# STM32_Schematics.net
KiCad netlist of a schematic drawn in Altium Designer
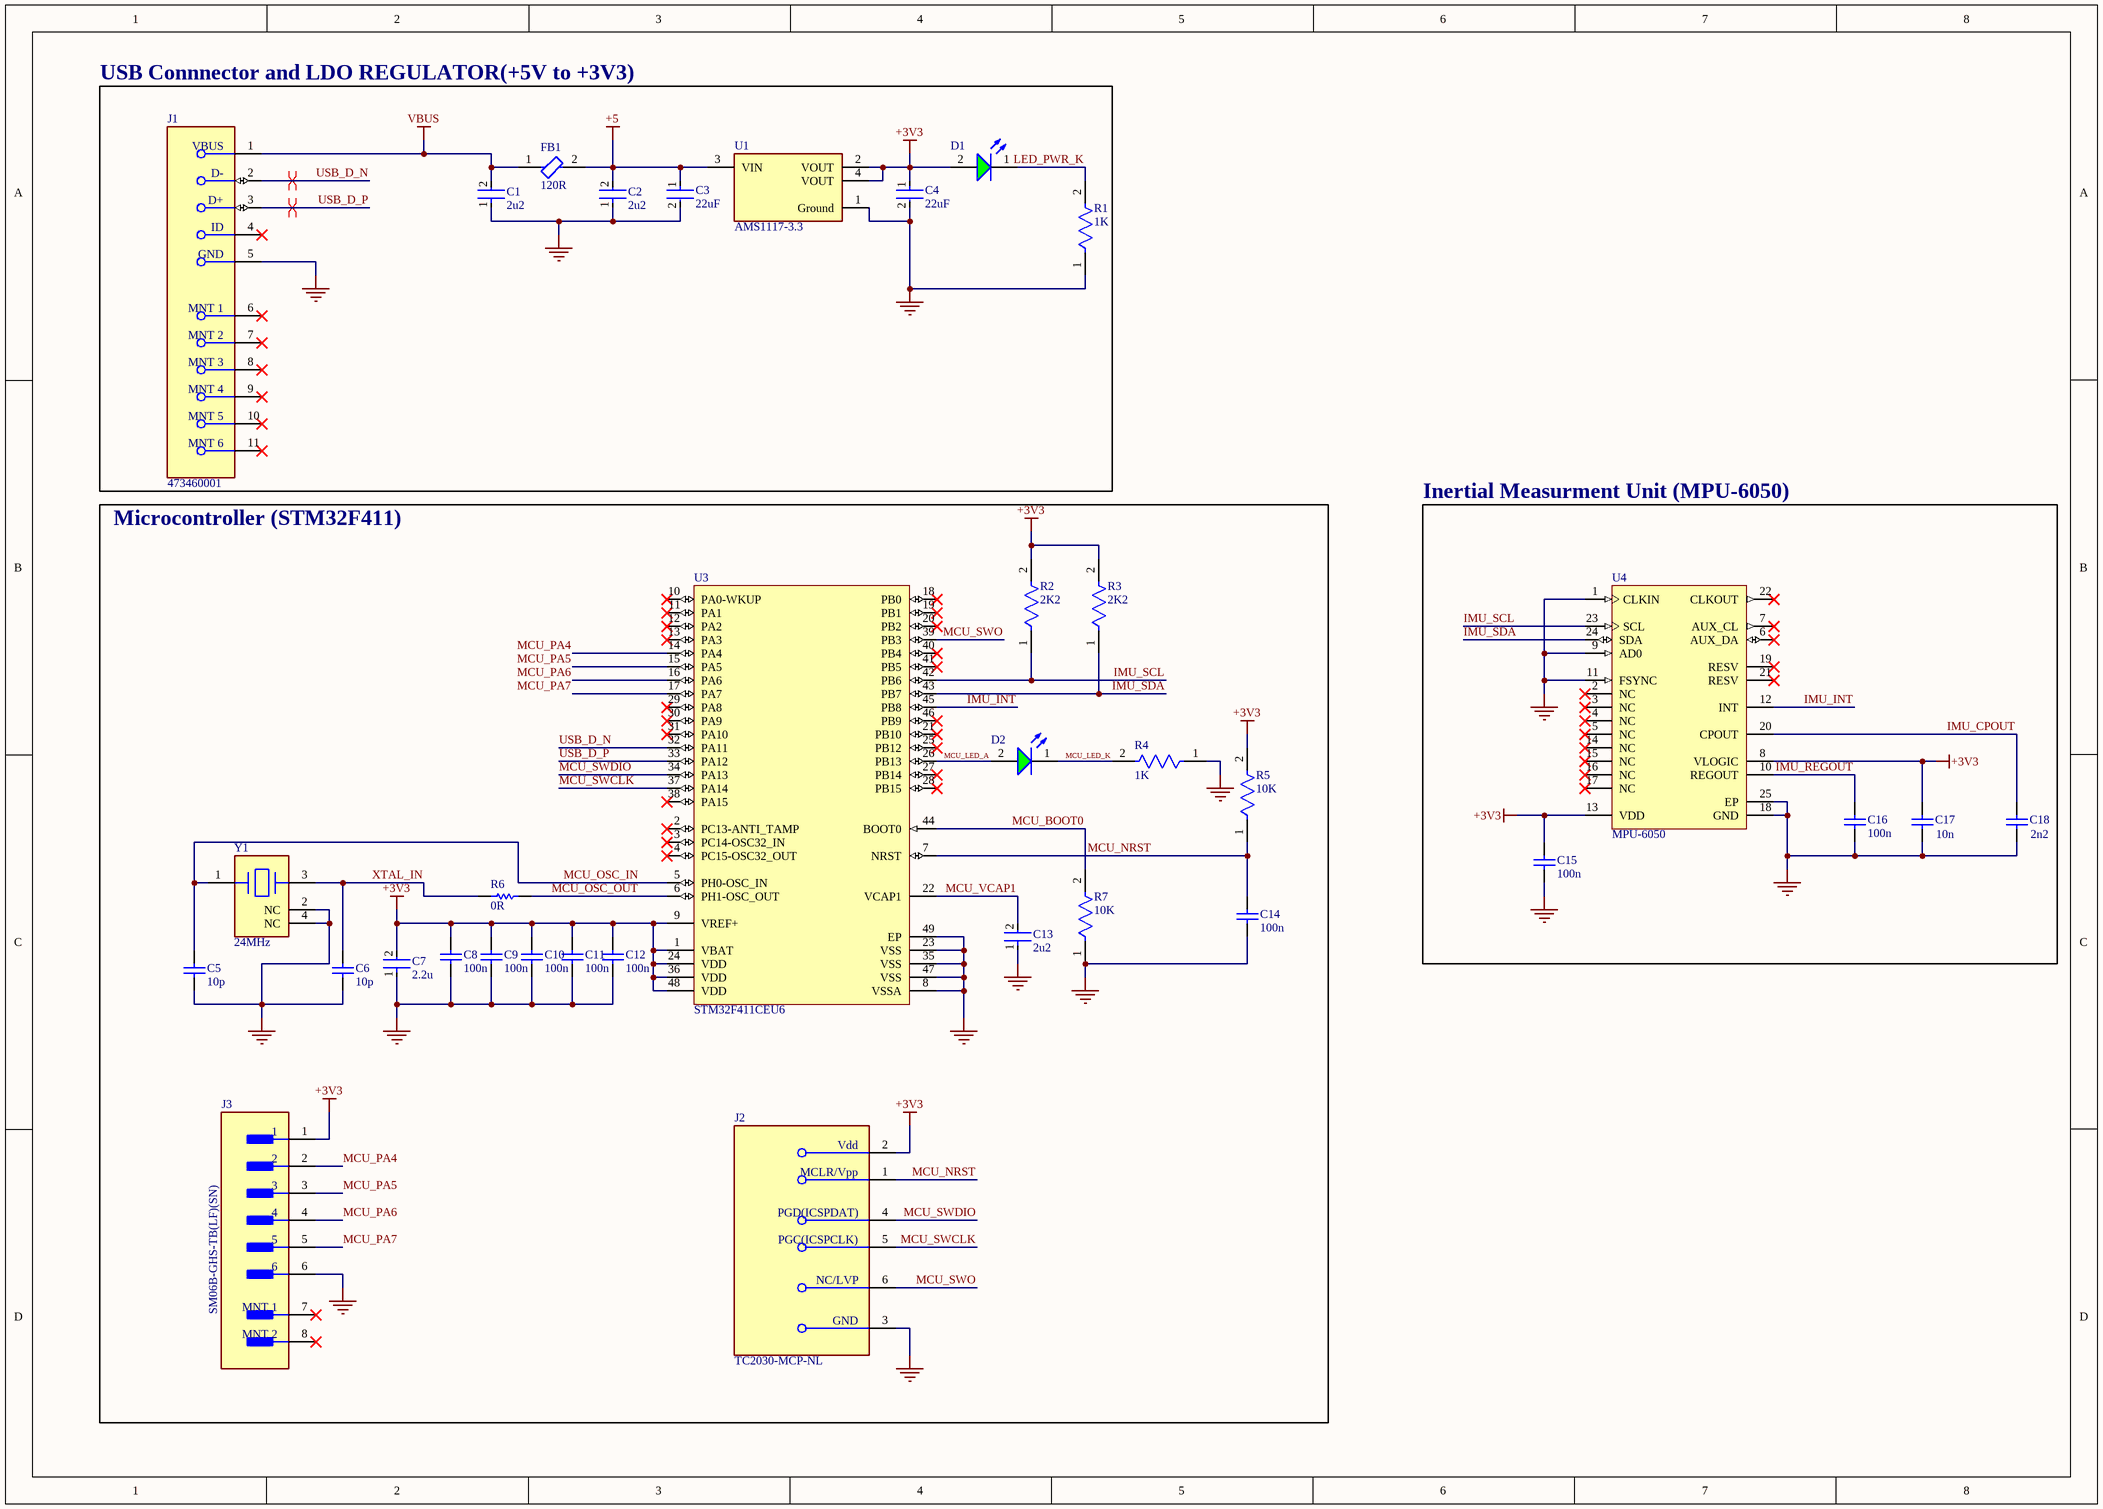
[diagram p0: STM32_Schematics.SchDoc]

(export (version "E")
  (design (tool "Eeschema 10.0.6"))
  (components
    (comp (ref "C1")
      (value "2u2")
      (footprint "FP-GRM188-0_2-IPC_B")
      (description "CAP CER 2.2UF 16V X7S 0603")
      (fields (field (name "TOLERANCE") "10%"))
      (libsource (lib "Altium Content Vault") (part "b4654b650e69147ec39a6b967a45e02"))
    )
    (comp (ref "C2")
      (value "2u2")
      (footprint "FP-GRM188-0_2-IPC_B")
      (description "CAP CER 2.2UF 16V X7S 0603")
      (fields (field (name "TOLERANCE") "10%"))
      (libsource (lib "Altium Content Vault") (part "b4654b650e69147ec39a6b967a45e02"))
    )
    (comp (ref "C3")
      (value "22uF")
      (footprint "FP-GRM219-0_2-0_15-IPC_B")
      (description "Chip Multilayer Ceramic Capacitors for General Purpose, 0805, 22uF, X5R, 15%, 20%, 16V")
      (fields (field (name "TOLERANCE") "20%"))
      (libsource (lib "Altium Content Vault") (part "b4654b650e69147ec39a6b967a45e02"))
    )
    (comp (ref "C4")
      (value "22uF")
      (footprint "FP-GRM219-0_2-0_15-IPC_B")
      (description "Chip Multilayer Ceramic Capacitors for General Purpose, 0805, 22uF, X5R, 15%, 20%, 16V")
      (fields (field (name "TOLERANCE") "20%"))
      (libsource (lib "Altium Content Vault") (part "b4654b650e69147ec39a6b967a45e02"))
    )
    (comp (ref "C5")
      (value "10p")
      (footprint "CAPC1005X55X25NL05T05")
      (fields (field (name "PART NUMBER") "VJ0402A100FXQCW1BC") (field (name "MANUFACTURER") "Vitramon"))
      (libsource (lib "Altium Content Vault") (part "CAP"))
    )
    (comp (ref "C6")
      (value "10p")
      (footprint "CAPC1005X55X25NL05T05")
      (fields (field (name "PART NUMBER") "VJ0402A100FXQCW1BC") (field (name "MANUFACTURER") "Vitramon"))
      (libsource (lib "Altium Content Vault") (part "CAP"))
    )
    (comp (ref "C7")
      (value "2.2u")
      (footprint "FP-GRM188-0_2-IPC_B")
      (description "CAP CER 2.2UF 16V X7S 0603")
      (fields (field (name "TOLERANCE") "10%"))
      (libsource (lib "Altium Content Vault") (part "b4654b650e69147ec39a6b967a45e02"))
    )
    (comp (ref "C8")
      (value "100n")
      (footprint "CAPC1050X55X23ML05T13")
      (description "Chip Capacitor, 100 nF, +/- 10%, 16 V, -55 to 125 degC, 0402 (1005 Metric), RoHS, Tape and Reel")
      (fields (field (name "MANUFACTURER") "Samsung Electro-Mechanics"))
      (libsource (lib "Altium Content Vault") (part "CAP-NP-2"))
    )
    (comp (ref "C9")
      (value "100n")
      (footprint "CAPC1050X55X23ML05T13")
      (description "Chip Capacitor, 100 nF, +/- 10%, 16 V, -55 to 125 degC, 0402 (1005 Metric), RoHS, Tape and Reel")
      (fields (field (name "MANUFACTURER") "Samsung Electro-Mechanics"))
      (libsource (lib "Altium Content Vault") (part "CAP-NP-2"))
    )
    (comp (ref "C10")
      (value "100n")
      (footprint "CAPC1050X55X23ML05T13")
      (description "Chip Capacitor, 100 nF, +/- 10%, 16 V, -55 to 125 degC, 0402 (1005 Metric), RoHS, Tape and Reel")
      (fields (field (name "MANUFACTURER") "Samsung Electro-Mechanics"))
      (libsource (lib "Altium Content Vault") (part "CAP-NP-2"))
    )
    (comp (ref "C11")
      (value "100n")
      (footprint "CAPC1050X55X23ML05T13")
      (description "Chip Capacitor, 100 nF, +/- 10%, 16 V, -55 to 125 degC, 0402 (1005 Metric), RoHS, Tape and Reel")
      (fields (field (name "MANUFACTURER") "Samsung Electro-Mechanics"))
      (libsource (lib "Altium Content Vault") (part "CAP-NP-2"))
    )
    (comp (ref "C12")
      (value "100n")
      (footprint "CAPC1050X55X23ML05T13")
      (description "Chip Capacitor, 100 nF, +/- 10%, 16 V, -55 to 125 degC, 0402 (1005 Metric), RoHS, Tape and Reel")
      (fields (field (name "MANUFACTURER") "Samsung Electro-Mechanics"))
      (libsource (lib "Altium Content Vault") (part "CAP-NP-2"))
    )
    (comp (ref "C13")
      (value "2u2")
      (footprint "FP-GRM188-0_2-IPC_B")
      (description "CAP CER 2.2UF 16V X7S 0603")
      (fields (field (name "TOLERANCE") "10%"))
      (libsource (lib "Altium Content Vault") (part "b4654b650e69147ec39a6b967a45e02"))
    )
    (comp (ref "C14")
      (value "100n")
      (footprint "CAPC1050X55X23ML05T13")
      (description "Chip Capacitor, 100 nF, +/- 10%, 16 V, -55 to 125 degC, 0402 (1005 Metric), RoHS, Tape and Reel")
      (fields (field (name "MANUFACTURER") "Samsung Electro-Mechanics"))
      (libsource (lib "Altium Content Vault") (part "CAP-NP-2"))
    )
    (comp (ref "C15")
      (value "100n")
      (footprint "CAPC1050X55X23ML05T13")
      (description "Chip Capacitor, 100 nF, +/- 10%, 16 V, -55 to 125 degC, 0402 (1005 Metric), RoHS, Tape and Reel")
      (fields (field (name "MANUFACTURER") "Samsung Electro-Mechanics"))
      (libsource (lib "Altium Content Vault") (part "CAP-NP-2"))
    )
    (comp (ref "C16")
      (value "100n")
      (footprint "CAPC1050X55X23ML05T13")
      (description "Chip Capacitor, 100 nF, +/- 10%, 16 V, -55 to 125 degC, 0402 (1005 Metric), RoHS, Tape and Reel")
      (fields (field (name "MANUFACTURER") "Samsung Electro-Mechanics"))
      (libsource (lib "Altium Content Vault") (part "CAP-NP-2"))
    )
    (comp (ref "C17")
      (value "10n")
      (footprint "CAPC1005X55X25LL05T10")
      (description "Chip Capacitor, 10 nF, 16 V, 10%, -55 to 125 degC, 0402 (1005 Metric), RoHS, Tape and Reel")
      (fields (field (name "MANUFACTURER") "Murata"))
      (libsource (lib "Altium Content Vault") (part "CAP-NP-2"))
    )
    (comp (ref "C18")
      (value "2n2")
      (footprint "CAPC1005X55X25LL05T10")
      (description "Chip Capacitor, 2.2nF, 16 V, 10%, -55 to 125 degC, 0402 (1005 Metric), RoHS, Tape and Reel")
      (fields (field (name "MANUFACTURER") "Murata"))
      (libsource (lib "Altium Content Vault") (part "CAP-NP-2"))
    )
    (comp (ref "D1")
      (value "150040VS73240")
      (footprint "WL-SMCC_0402_L1W0.5H0.4")
      (description "Wurth Elektronik LED, WL-SMCC, 1005 (0402), 570 nm, 1 x 0.5 x 0.4mm")
      (libsource (lib "Altium Content Vault") (part "LED_Green_2A-1K"))
    )
    (comp (ref "D2")
      (value "150040VS73240")
      (footprint "WL-SMCC_0402_L1W0.5H0.4")
      (description "Wurth Elektronik LED, WL-SMCC, 1005 (0402), 570 nm, 1 x 0.5 x 0.4mm")
      (libsource (lib "Altium Content Vault") (part "LED_Green_2A-1K"))
    )
    (comp (ref "FB1")
      (value "120R")
      (footprint "FP-BLM18-0_15-t0_8-IPC_B")
      (description "Chip Ferrite Bead, 0603, 120Ω @ 100MHz, 0.18Ω, 25%, 800mA")
      (fields (field (name "TOLERANCE") "25%"))
      (libsource (lib "Altium Content Vault") (part "5f30dd21d616792df468990f7003faa"))
    )
    (comp (ref "J1")
      (value "473460001")
      (footprint "FP-473460001-MFG")
      (description "CONN RCPT USB2.0 MICRO B SMD R/A")
      (fields
        (field (name "OCTOPART") "https://octopart.com/47346-0001-molex-7164928")
        (field (name "MANUFACTURER") "Molex")
      )
      (libsource (lib "Altium Content Vault") (part "53ae1f1d9b557310b43ca686e5bb76a"))
    )
    (comp (ref "J2")
      (value "TC2030-MCP-NL")
      (footprint "FP-TC2030-MCP-NL-MFG")
      (description "CABLE TAG-CONNECT IN-CIRCUIT")
      (libsource (lib "Altium Content Vault") (part "da277a6d6cd793b3b4415b302df1337"))
    )
    (comp (ref "J3")
      (value "SM06B-GHS-TB(LF)(SN)")
      (footprint "FP-SM06B-GHS-TB_LF_SN-MFG")
      (description "CONN HEADER SMD R/A 6POS 1.25MM")
      (libsource (lib "Altium Content Vault") (part "ed24c53d9ba001d1a2a686240a95171"))
    )
    (comp (ref "R1")
      (value "1K")
      (footprint "FP-RC0402-0_4-IPC_A")
      (description "RES 1K OHM 1% 1/16W 0402")
      (fields (field (name "TOLERANCE") "1%"))
      (libsource (lib "Altium Content Vault") (part "1029c3af85768c4190bb7ad29bc67b5"))
    )
    (comp (ref "R2")
      (value "2K2")
      (footprint "FP-AC0402-IPC_C")
      (description "RES 2.2kΩ ±1% 0.125W 0402")
      (libsource (lib "Altium Content Vault") (part "1029c3af85768c4190bb7ad29bc67b5"))
    )
    (comp (ref "R3")
      (value "2K2")
      (footprint "FP-AC0402-IPC_C")
      (description "RES 2.2kΩ ±1% 0.125W 0402")
      (libsource (lib "Altium Content Vault") (part "1029c3af85768c4190bb7ad29bc67b5"))
    )
    (comp (ref "R4")
      (value "1K")
      (footprint "FP-RC0402-0_4-IPC_A")
      (description "RES 1K OHM 1% 1/16W 0402")
      (fields (field (name "TOLERANCE") "1%"))
      (libsource (lib "Altium Content Vault") (part "1029c3af85768c4190bb7ad29bc67b5"))
    )
    (comp (ref "R5")
      (value "10K")
      (footprint "FP-CRCW0402-C-e3-IPC_C")
      (description "RES 10K OHM 1% 1/16W 0402")
      (fields (field (name "TOLERANCE") "1%"))
      (libsource (lib "Altium Content Vault") (part "1029c3af85768c4190bb7ad29bc67b5"))
    )
    (comp (ref "R6")
      (value "0R")
      (footprint "RESC1005X40X25LL05T10")
      (description "Chip Resistor, 0 Ohm, +/- 5%, -55 to 125 degC, 0402 (1005 Metric), RoHS, Tape and Reel")
      (fields (field (name "MANUFACTURER") "Samsung Electro-Mechanics"))
      (libsource (lib "Altium Content Vault") (part "RES-2"))
    )
    (comp (ref "R7")
      (value "10K")
      (footprint "FP-CRCW0402-C-e3-IPC_C")
      (description "RES 10K OHM 1% 1/16W 0402")
      (fields (field (name "TOLERANCE") "1%"))
      (libsource (lib "Altium Content Vault") (part "1029c3af85768c4190bb7ad29bc67b5"))
    )
    (comp (ref "U1")
      (value "AMS1117-3.3")
      (footprint "FP-AMS1117-IPC_C")
      (description "LDO Voltage Regulators 1A, 3.3V")
      (fields
        (field (name "OCTOPART") "https://octopart.com/ams1117-3.3-advanced+monolithic+systems-25899300")
        (field (name "MANUFACTURER") "Advanced Monolithic Systems")
      )
      (libsource (lib "Altium Content Vault") (part "8bdbb5f8e77002000e30dd2845d0354"))
    )
    (comp (ref "U3")
      (value "STM32F411CEU6")
      (footprint "STM-UFQFPN48_L")
      (libsource (lib "Altium Content Vault") (part "MC-ARM-STM32F411-UFQFPN48"))
    )
    (comp (ref "U4")
      (value "MPU-6050")
      (footprint "IS-QFN-24_V")
      (fields (field (name "MANUFACTURER") "InvenSense"))
      (libsource (lib "Altium Content Vault") (part "IS-MPU-6050-QFN-24"))
    )
    (comp (ref "Y1")
      (value "24MHz")
      (footprint "FP-XRCGB_F_N-MFG")
      (description "CRYSTAL 24.0000MHZ 6PF SMD")
      (fields (field (name "TOLERANCE") "30ppm"))
      (libsource (lib "Altium Content Vault") (part "13d16a3a70fb0809ccfd81e284aeb9d"))
    )
  )
  (nets
    (net (code "1") (name "+3V3") (class "Default")
      (node (ref "C10") (pin "2") (pinfunction "2_2") (pintype "passive"))
      (node (ref "C11") (pin "2") (pinfunction "2_2") (pintype "passive"))
      (node (ref "C12") (pin "2") (pinfunction "2_2") (pintype "passive"))
      (node (ref "C15") (pin "2") (pinfunction "2_2") (pintype "passive"))
      (node (ref "C17") (pin "2") (pinfunction "2_2") (pintype "passive"))
      (node (ref "C4") (pin "1") (pinfunction "1_1") (pintype "passive"))
      (node (ref "C7") (pin "2") (pinfunction "2_2") (pintype "passive"))
      (node (ref "C8") (pin "2") (pinfunction "2_2") (pintype "passive"))
      (node (ref "C9") (pin "2") (pinfunction "2_2") (pintype "passive"))
      (node (ref "D1") (pin "2") (pinfunction "A_2") (pintype "passive"))
      (node (ref "J2") (pin "2") (pinfunction "Vdd_2") (pintype "passive"))
      (node (ref "J3") (pin "1") (pinfunction "1_1") (pintype "passive"))
      (node (ref "R2") (pin "2") (pinfunction "2_2") (pintype "passive"))
      (node (ref "R3") (pin "2") (pinfunction "2_2") (pintype "passive"))
      (node (ref "R5") (pin "2") (pinfunction "2_2") (pintype "passive"))
      (node (ref "U1") (pin "2") (pinfunction "VOUT_2") (pintype "passive"))
      (node (ref "U1") (pin "4") (pinfunction "VOUT_4") (pintype "passive"))
      (node (ref "U3") (pin "1") (pinfunction "VBAT_1") (pintype "power_in"))
      (node (ref "U3") (pin "24") (pinfunction "VDD_24") (pintype "power_in"))
      (node (ref "U3") (pin "36") (pinfunction "VDD_36") (pintype "power_in"))
      (node (ref "U3") (pin "48") (pinfunction "VDD_48") (pintype "power_in"))
      (node (ref "U3") (pin "9") (pinfunction "VREF+_9") (pintype "power_in"))
      (node (ref "U4") (pin "13") (pinfunction "VDD_13") (pintype "power_in"))
      (node (ref "U4") (pin "8") (pinfunction "VLOGIC_8") (pintype "power_in"))
    )
    (net (code "2") (name "+5") (class "Default")
      (node (ref "C2") (pin "2") (pinfunction "2_2") (pintype "passive"))
      (node (ref "C3") (pin "1") (pinfunction "1_1") (pintype "passive"))
      (node (ref "FB1") (pin "2") (pinfunction "2_2") (pintype "passive"))
      (node (ref "U1") (pin "3") (pinfunction "VIN_3") (pintype "power_in"))
    )
    (net (code "3") (name "/IMU_CPOUT") (class "Default")
      (node (ref "C18") (pin "2") (pinfunction "2_2") (pintype "passive"))
      (node (ref "U4") (pin "20") (pinfunction "CPOUT_20") (pintype "passive"))
    )
    (net (code "4") (name "/IMU_INT") (class "Default")
      (node (ref "U3") (pin "45") (pinfunction "PB8_45") (pintype "bidirectional"))
      (node (ref "U4") (pin "12") (pinfunction "INT_12") (pintype "open_collector"))
    )
    (net (code "5") (name "/IMU_REGOUT") (class "Default")
      (node (ref "C16") (pin "1") (pinfunction "1_1") (pintype "passive"))
      (node (ref "U4") (pin "10") (pinfunction "REGOUT_10") (pintype "passive"))
    )
    (net (code "6") (name "/IMU_SCL") (class "Default")
      (node (ref "R2") (pin "1") (pinfunction "1_1") (pintype "passive"))
      (node (ref "U3") (pin "42") (pinfunction "PB6_42") (pintype "bidirectional"))
      (node (ref "U4") (pin "23") (pinfunction "SCL_23") (pintype "input"))
    )
    (net (code "7") (name "/IMU_SDA") (class "Default")
      (node (ref "R3") (pin "1") (pinfunction "1_1") (pintype "passive"))
      (node (ref "U3") (pin "43") (pinfunction "PB7_43") (pintype "bidirectional"))
      (node (ref "U4") (pin "24") (pinfunction "SDA_24") (pintype "bidirectional"))
    )
    (net (code "8") (name "/LED_PWR_K") (class "Default")
      (node (ref "D1") (pin "1") (pinfunction "K_1") (pintype "passive"))
      (node (ref "R1") (pin "2") (pinfunction "2_2") (pintype "passive"))
    )
    (net (code "9") (name "/MCU_BOOT0") (class "Default")
      (node (ref "R7") (pin "2") (pinfunction "2_2") (pintype "passive"))
      (node (ref "U3") (pin "44") (pinfunction "BOOT0_44") (pintype "input"))
    )
    (net (code "10") (name "/MCU_LED_A") (class "Default")
      (node (ref "D2") (pin "2") (pinfunction "A_2") (pintype "passive"))
      (node (ref "U3") (pin "26") (pinfunction "PB13_26") (pintype "bidirectional"))
    )
    (net (code "11") (name "/MCU_LED_K") (class "Default")
      (node (ref "D2") (pin "1") (pinfunction "K_1") (pintype "passive"))
      (node (ref "R4") (pin "2") (pinfunction "2_2") (pintype "passive"))
    )
    (net (code "12") (name "/MCU_NRST") (class "Default")
      (node (ref "C14") (pin "2") (pinfunction "2_2") (pintype "passive"))
      (node (ref "J2") (pin "1") (pinfunction "MCLR/Vpp_1") (pintype "passive"))
      (node (ref "R5") (pin "1") (pinfunction "1_1") (pintype "passive"))
      (node (ref "U3") (pin "7") (pinfunction "NRST_7") (pintype "bidirectional"))
    )
    (net (code "13") (name "/MCU_OSC_IN") (class "Default")
      (node (ref "C5") (pin "2") (pinfunction "2_2") (pintype "passive"))
      (node (ref "U3") (pin "5") (pinfunction "PH0-OSC_IN_5") (pintype "bidirectional"))
      (node (ref "Y1") (pin "1") (pinfunction "1_Input/Output_1") (pintype "passive"))
    )
    (net (code "14") (name "/MCU_OSC_OUT") (class "Default")
      (node (ref "R6") (pin "2") (pinfunction "2_2") (pintype "passive"))
      (node (ref "U3") (pin "6") (pinfunction "PH1-OSC_OUT_6") (pintype "bidirectional"))
    )
    (net (code "15") (name "/MCU_PA4") (class "Default")
      (node (ref "J3") (pin "2") (pinfunction "2_2") (pintype "passive"))
      (node (ref "U3") (pin "14") (pinfunction "PA4_14") (pintype "bidirectional"))
    )
    (net (code "16") (name "/MCU_PA5") (class "Default")
      (node (ref "J3") (pin "3") (pinfunction "3_3") (pintype "passive"))
      (node (ref "U3") (pin "15") (pinfunction "PA5_15") (pintype "bidirectional"))
    )
    (net (code "17") (name "/MCU_PA6") (class "Default")
      (node (ref "J3") (pin "4") (pinfunction "4_4") (pintype "passive"))
      (node (ref "U3") (pin "16") (pinfunction "PA6_16") (pintype "bidirectional"))
    )
    (net (code "18") (name "/MCU_PA7") (class "Default")
      (node (ref "J3") (pin "5") (pinfunction "5_5") (pintype "passive"))
      (node (ref "U3") (pin "17") (pinfunction "PA7_17") (pintype "bidirectional"))
    )
    (net (code "19") (name "/MCU_SWCLK") (class "Default")
      (node (ref "J2") (pin "5") (pinfunction "PGC(ICSPCLK)_5") (pintype "passive"))
      (node (ref "U3") (pin "37") (pinfunction "PA14_37") (pintype "bidirectional"))
    )
    (net (code "20") (name "/MCU_SWDIO") (class "Default")
      (node (ref "J2") (pin "4") (pinfunction "PGD(ICSPDAT)_4") (pintype "passive"))
      (node (ref "U3") (pin "34") (pinfunction "PA13_34") (pintype "bidirectional"))
    )
    (net (code "21") (name "/MCU_SWO") (class "Default")
      (node (ref "J2") (pin "6") (pinfunction "NC/LVP_6") (pintype "passive"))
      (node (ref "U3") (pin "39") (pinfunction "PB3_39") (pintype "bidirectional"))
    )
    (net (code "22") (name "/MCU_VCAP1") (class "Default")
      (node (ref "C13") (pin "2") (pinfunction "2_2") (pintype "passive"))
      (node (ref "U3") (pin "22") (pinfunction "VCAP1_22") (pintype "passive"))
    )
    (net (code "23") (name "/USB_D_N") (class "Default")
      (node (ref "J1") (pin "2") (pinfunction "D-_2") (pintype "bidirectional"))
      (node (ref "U3") (pin "32") (pinfunction "PA11_32") (pintype "bidirectional"))
    )
    (net (code "24") (name "/USB_D_P") (class "Default")
      (node (ref "J1") (pin "3") (pinfunction "D+_3") (pintype "bidirectional"))
      (node (ref "U3") (pin "33") (pinfunction "PA12_33") (pintype "bidirectional"))
    )
    (net (code "25") (name "/XTAL_IN") (class "Default")
      (node (ref "C6") (pin "2") (pinfunction "2_2") (pintype "passive"))
      (node (ref "R6") (pin "1") (pinfunction "1_1") (pintype "passive"))
      (node (ref "Y1") (pin "3") (pinfunction "2_Input/Output_3") (pintype "passive"))
    )
    (net (code "26") (name "GND") (class "Default")
      (node (ref "C1") (pin "1") (pinfunction "1_1") (pintype "passive"))
      (node (ref "C10") (pin "1") (pinfunction "1_1") (pintype "passive"))
      (node (ref "C11") (pin "1") (pinfunction "1_1") (pintype "passive"))
      (node (ref "C12") (pin "1") (pinfunction "1_1") (pintype "passive"))
      (node (ref "C13") (pin "1") (pinfunction "1_1") (pintype "passive"))
      (node (ref "C14") (pin "1") (pinfunction "1_1") (pintype "passive"))
      (node (ref "C15") (pin "1") (pinfunction "1_1") (pintype "passive"))
      (node (ref "C16") (pin "2") (pinfunction "2_2") (pintype "passive"))
      (node (ref "C17") (pin "1") (pinfunction "1_1") (pintype "passive"))
      (node (ref "C18") (pin "1") (pinfunction "1_1") (pintype "passive"))
      (node (ref "C2") (pin "1") (pinfunction "1_1") (pintype "passive"))
      (node (ref "C3") (pin "2") (pinfunction "2_2") (pintype "passive"))
      (node (ref "C4") (pin "2") (pinfunction "2_2") (pintype "passive"))
      (node (ref "C5") (pin "1") (pinfunction "1_1") (pintype "passive"))
      (node (ref "C6") (pin "1") (pinfunction "1_1") (pintype "passive"))
      (node (ref "C7") (pin "1") (pinfunction "1_1") (pintype "passive"))
      (node (ref "C8") (pin "1") (pinfunction "1_1") (pintype "passive"))
      (node (ref "C9") (pin "1") (pinfunction "1_1") (pintype "passive"))
      (node (ref "J1") (pin "5") (pinfunction "GND_5") (pintype "power_in"))
      (node (ref "J2") (pin "3") (pinfunction "GND_3") (pintype "passive"))
      (node (ref "J3") (pin "6") (pinfunction "6_6") (pintype "passive"))
      (node (ref "R1") (pin "1") (pinfunction "1_1") (pintype "passive"))
      (node (ref "R4") (pin "1") (pinfunction "1_1") (pintype "passive"))
      (node (ref "R7") (pin "1") (pinfunction "1_1") (pintype "passive"))
      (node (ref "U1") (pin "1") (pinfunction "Ground_1") (pintype "power_in"))
      (node (ref "U3") (pin "23") (pinfunction "VSS_23") (pintype "power_in"))
      (node (ref "U3") (pin "35") (pinfunction "VSS_35") (pintype "power_in"))
      (node (ref "U3") (pin "47") (pinfunction "VSS_47") (pintype "power_in"))
      (node (ref "U3") (pin "49") (pinfunction "EP_49") (pintype "power_in"))
      (node (ref "U3") (pin "8") (pinfunction "VSSA_8") (pintype "power_in"))
      (node (ref "U4") (pin "1") (pinfunction "CLKIN_1") (pintype "input"))
      (node (ref "U4") (pin "11") (pinfunction "FSYNC_11") (pintype "input"))
      (node (ref "U4") (pin "18") (pinfunction "GND_18") (pintype "power_in"))
      (node (ref "U4") (pin "25") (pinfunction "EP_25") (pintype "power_in"))
      (node (ref "U4") (pin "9") (pinfunction "AD0_9") (pintype "input"))
      (node (ref "Y1") (pin "2") (pinfunction "NC_2") (pintype "passive"))
      (node (ref "Y1") (pin "4") (pinfunction "NC_4") (pintype "passive"))
    )
    (net (code "27") (name "VBUS") (class "Default")
      (node (ref "C1") (pin "2") (pinfunction "2_2") (pintype "passive"))
      (node (ref "FB1") (pin "1") (pinfunction "1_1") (pintype "passive"))
      (node (ref "J1") (pin "1") (pinfunction "VBUS_1") (pintype "power_in"))
    )
    (net (code "28") (name "unconnected-(J1-ID-Pad4)") (class "Default")
      (node (ref "J1") (pin "4") (pinfunction "ID_4") (pintype "passive+no_connect"))
    )
    (net (code "29") (name "unconnected-(J1-MNT_1-Pad6)") (class "Default")
      (node (ref "J1") (pin "6") (pinfunction "MNT_1_6") (pintype "passive+no_connect"))
    )
    (net (code "30") (name "unconnected-(J1-MNT_2-Pad7)") (class "Default")
      (node (ref "J1") (pin "7") (pinfunction "MNT_2_7") (pintype "passive+no_connect"))
    )
    (net (code "31") (name "unconnected-(J1-MNT_3-Pad8)") (class "Default")
      (node (ref "J1") (pin "8") (pinfunction "MNT_3_8") (pintype "passive+no_connect"))
    )
    (net (code "32") (name "unconnected-(J1-MNT_4-Pad9)") (class "Default")
      (node (ref "J1") (pin "9") (pinfunction "MNT_4_9") (pintype "passive+no_connect"))
    )
    (net (code "33") (name "unconnected-(J1-MNT_5-Pad10)") (class "Default")
      (node (ref "J1") (pin "10") (pinfunction "MNT_5_10") (pintype "passive+no_connect"))
    )
    (net (code "34") (name "unconnected-(J1-MNT_6-Pad11)") (class "Default")
      (node (ref "J1") (pin "11") (pinfunction "MNT_6_11") (pintype "passive+no_connect"))
    )
    (net (code "35") (name "unconnected-(J3-MNT_1-Pad7)") (class "Default")
      (node (ref "J3") (pin "7") (pinfunction "MNT_1_7") (pintype "passive+no_connect"))
    )
    (net (code "36") (name "unconnected-(J3-MNT_2-Pad8)") (class "Default")
      (node (ref "J3") (pin "8") (pinfunction "MNT_2_8") (pintype "passive+no_connect"))
    )
    (net (code "37") (name "unconnected-(U3-PA0-WKUP-Pad10)") (class "Default")
      (node (ref "U3") (pin "10") (pinfunction "PA0-WKUP_10") (pintype "bidirectional+no_connect"))
    )
    (net (code "38") (name "unconnected-(U3-PA1-Pad11)") (class "Default")
      (node (ref "U3") (pin "11") (pinfunction "PA1_11") (pintype "bidirectional+no_connect"))
    )
    (net (code "39") (name "unconnected-(U3-PA2-Pad12)") (class "Default")
      (node (ref "U3") (pin "12") (pinfunction "PA2_12") (pintype "bidirectional+no_connect"))
    )
    (net (code "40") (name "unconnected-(U3-PA3-Pad13)") (class "Default")
      (node (ref "U3") (pin "13") (pinfunction "PA3_13") (pintype "bidirectional+no_connect"))
    )
    (net (code "41") (name "unconnected-(U3-PA8-Pad29)") (class "Default")
      (node (ref "U3") (pin "29") (pinfunction "PA8_29") (pintype "bidirectional+no_connect"))
    )
    (net (code "42") (name "unconnected-(U3-PA9-Pad30)") (class "Default")
      (node (ref "U3") (pin "30") (pinfunction "PA9_30") (pintype "bidirectional+no_connect"))
    )
    (net (code "43") (name "unconnected-(U3-PA10-Pad31)") (class "Default")
      (node (ref "U3") (pin "31") (pinfunction "PA10_31") (pintype "bidirectional+no_connect"))
    )
    (net (code "44") (name "unconnected-(U3-PA15-Pad38)") (class "Default")
      (node (ref "U3") (pin "38") (pinfunction "PA15_38") (pintype "bidirectional+no_connect"))
    )
    (net (code "45") (name "unconnected-(U3-PB0-Pad18)") (class "Default")
      (node (ref "U3") (pin "18") (pinfunction "PB0_18") (pintype "bidirectional+no_connect"))
    )
    (net (code "46") (name "unconnected-(U3-PB1-Pad19)") (class "Default")
      (node (ref "U3") (pin "19") (pinfunction "PB1_19") (pintype "bidirectional+no_connect"))
    )
    (net (code "47") (name "unconnected-(U3-PB2-Pad20)") (class "Default")
      (node (ref "U3") (pin "20") (pinfunction "PB2_20") (pintype "bidirectional+no_connect"))
    )
    (net (code "48") (name "unconnected-(U3-PB4-Pad40)") (class "Default")
      (node (ref "U3") (pin "40") (pinfunction "PB4_40") (pintype "bidirectional+no_connect"))
    )
    (net (code "49") (name "unconnected-(U3-PB5-Pad41)") (class "Default")
      (node (ref "U3") (pin "41") (pinfunction "PB5_41") (pintype "bidirectional+no_connect"))
    )
    (net (code "50") (name "unconnected-(U3-PB9-Pad46)") (class "Default")
      (node (ref "U3") (pin "46") (pinfunction "PB9_46") (pintype "bidirectional+no_connect"))
    )
    (net (code "51") (name "unconnected-(U3-PB10-Pad21)") (class "Default")
      (node (ref "U3") (pin "21") (pinfunction "PB10_21") (pintype "bidirectional+no_connect"))
    )
    (net (code "52") (name "unconnected-(U3-PB12-Pad25)") (class "Default")
      (node (ref "U3") (pin "25") (pinfunction "PB12_25") (pintype "bidirectional+no_connect"))
    )
    (net (code "53") (name "unconnected-(U3-PB14-Pad27)") (class "Default")
      (node (ref "U3") (pin "27") (pinfunction "PB14_27") (pintype "bidirectional+no_connect"))
    )
    (net (code "54") (name "unconnected-(U3-PB15-Pad28)") (class "Default")
      (node (ref "U3") (pin "28") (pinfunction "PB15_28") (pintype "bidirectional+no_connect"))
    )
    (net (code "55") (name "unconnected-(U3-PC13-ANTI_TAMP-Pad2)") (class "Default")
      (node (ref "U3") (pin "2") (pinfunction "PC13-ANTI_TAMP_2") (pintype "bidirectional+no_connect"))
    )
    (net (code "56") (name "unconnected-(U3-PC14-OSC32_IN-Pad3)") (class "Default")
      (node (ref "U3") (pin "3") (pinfunction "PC14-OSC32_IN_3") (pintype "bidirectional+no_connect"))
    )
    (net (code "57") (name "unconnected-(U3-PC15-OSC32_OUT-Pad4)") (class "Default")
      (node (ref "U3") (pin "4") (pinfunction "PC15-OSC32_OUT_4") (pintype "bidirectional+no_connect"))
    )
    (net (code "58") (name "unconnected-(U4-AUX_CL-Pad7)") (class "Default")
      (node (ref "U4") (pin "7") (pinfunction "AUX_CL_7") (pintype "output+no_connect"))
    )
    (net (code "59") (name "unconnected-(U4-AUX_DA-Pad6)") (class "Default")
      (node (ref "U4") (pin "6") (pinfunction "AUX_DA_6") (pintype "bidirectional+no_connect"))
    )
    (net (code "60") (name "unconnected-(U4-CLKOUT-Pad22)") (class "Default")
      (node (ref "U4") (pin "22") (pinfunction "CLKOUT_22") (pintype "output+no_connect"))
    )
    (net (code "61") (name "unconnected-(U4-NC-Pad2)") (class "Default")
      (node (ref "U4") (pin "2") (pinfunction "NC_2") (pintype "passive+no_connect"))
    )
    (net (code "62") (name "unconnected-(U4-NC-Pad3)") (class "Default")
      (node (ref "U4") (pin "3") (pinfunction "NC_3") (pintype "passive+no_connect"))
    )
    (net (code "63") (name "unconnected-(U4-NC-Pad4)") (class "Default")
      (node (ref "U4") (pin "4") (pinfunction "NC_4") (pintype "passive+no_connect"))
    )
    (net (code "64") (name "unconnected-(U4-NC-Pad5)") (class "Default")
      (node (ref "U4") (pin "5") (pinfunction "NC_5") (pintype "passive+no_connect"))
    )
    (net (code "65") (name "unconnected-(U4-NC-Pad14)") (class "Default")
      (node (ref "U4") (pin "14") (pinfunction "NC_14") (pintype "passive+no_connect"))
    )
    (net (code "66") (name "unconnected-(U4-NC-Pad15)") (class "Default")
      (node (ref "U4") (pin "15") (pinfunction "NC_15") (pintype "passive+no_connect"))
    )
    (net (code "67") (name "unconnected-(U4-NC-Pad16)") (class "Default")
      (node (ref "U4") (pin "16") (pinfunction "NC_16") (pintype "passive+no_connect"))
    )
    (net (code "68") (name "unconnected-(U4-NC-Pad17)") (class "Default")
      (node (ref "U4") (pin "17") (pinfunction "NC_17") (pintype "passive+no_connect"))
    )
    (net (code "69") (name "unconnected-(U4-RESV-Pad19)") (class "Default")
      (node (ref "U4") (pin "19") (pinfunction "RESV_19") (pintype "passive+no_connect"))
    )
    (net (code "70") (name "unconnected-(U4-RESV-Pad21)") (class "Default")
      (node (ref "U4") (pin "21") (pinfunction "RESV_21") (pintype "passive+no_connect"))
    )
  )
)
